# usb64.net
KiCad netlist of a schematic drawn in EAGLE
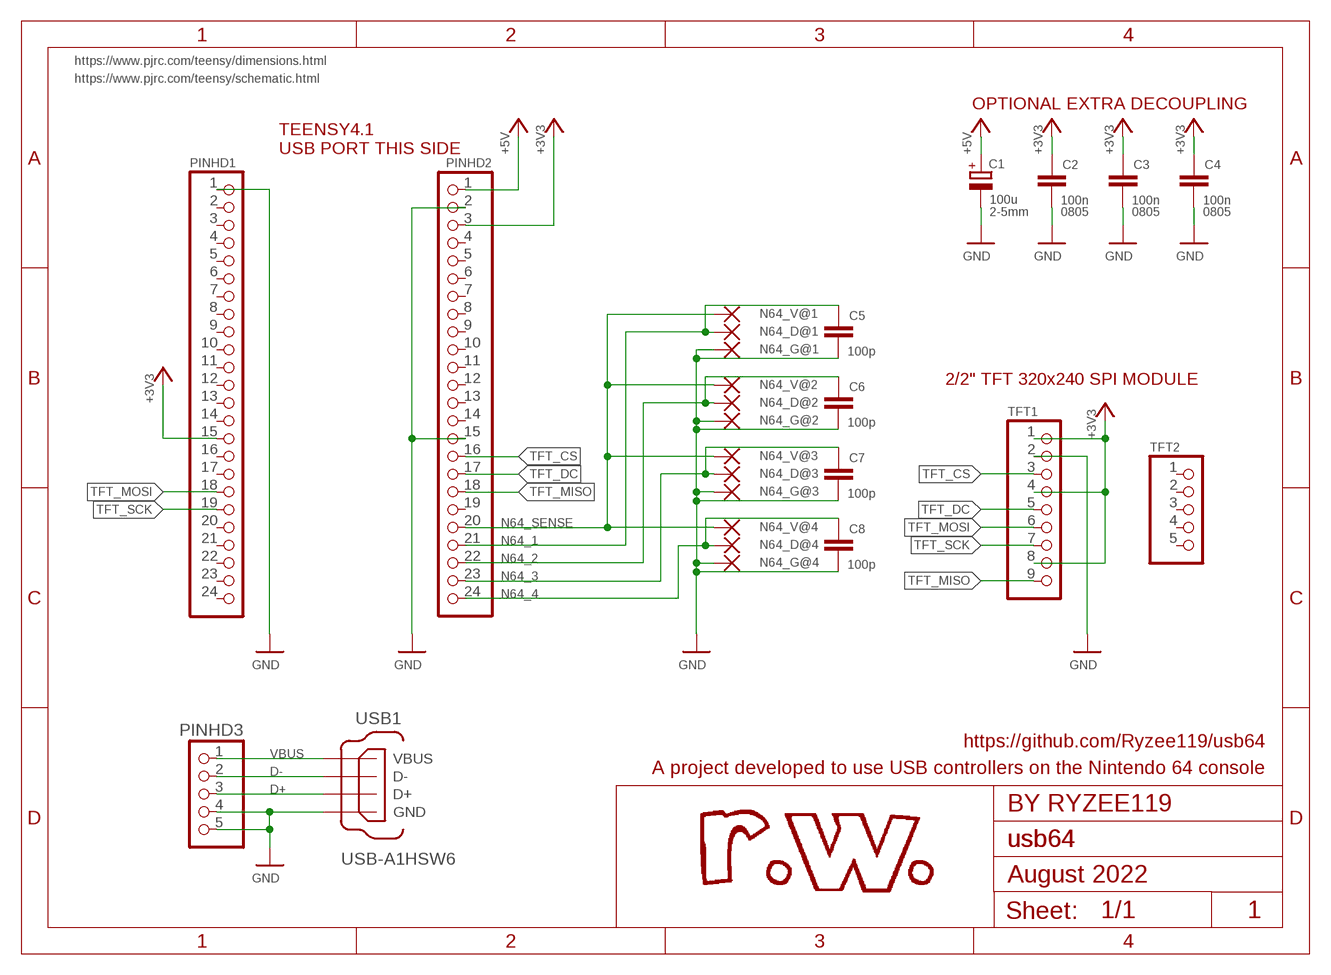
[diagram p0: schematic, sheet 1]

(export (version "E")
  (design (tool "Eeschema 10.0.6"))
  (components
    (comp (ref "C1")
      (value "100u")
      (footprint "eagle-import:E2-5")
      (libsource (lib "eagle-import") (part "CPOL-EUE2-5"))
    )
    (comp (ref "C2")
      (value "100n")
      (footprint "eagle-import:C0805K")
      (libsource (lib "eagle-import") (part "C-EUC0805K"))
    )
    (comp (ref "C3")
      (value "100n")
      (footprint "eagle-import:C0805K")
      (libsource (lib "eagle-import") (part "C-EUC0805K"))
    )
    (comp (ref "C4")
      (value "100n")
      (footprint "eagle-import:C0805K")
      (libsource (lib "eagle-import") (part "C-EUC0805K"))
    )
    (comp (ref "C5")
      (value "100p")
      (footprint "eagle-import:C0805K")
      (libsource (lib "eagle-import") (part "C-EUC0805K"))
    )
    (comp (ref "C6")
      (value "100p")
      (footprint "eagle-import:C0805K")
      (libsource (lib "eagle-import") (part "C-EUC0805K"))
    )
    (comp (ref "C7")
      (value "100p")
      (footprint "eagle-import:C0805K")
      (libsource (lib "eagle-import") (part "C-EUC0805K"))
    )
    (comp (ref "C8")
      (value "100p")
      (footprint "eagle-import:C0805K")
      (libsource (lib "eagle-import") (part "C-EUC0805K"))
    )
    (comp (ref "N64_D@1")
      (value "SMD2")
      (footprint "eagle-import:SMD1,27-2,54")
      (libsource (lib "eagle-import") (part "SMD2"))
    )
    (comp (ref "N64_D@2")
      (value "SMD2")
      (footprint "eagle-import:SMD1,27-2,54")
      (libsource (lib "eagle-import") (part "SMD2"))
    )
    (comp (ref "N64_D@3")
      (value "SMD2")
      (footprint "eagle-import:SMD1,27-2,54")
      (libsource (lib "eagle-import") (part "SMD2"))
    )
    (comp (ref "N64_D@4")
      (value "SMD2")
      (footprint "eagle-import:SMD1,27-2,54")
      (libsource (lib "eagle-import") (part "SMD2"))
    )
    (comp (ref "N64_G@1")
      (value "SMD2")
      (footprint "eagle-import:SMD1,27-2,54")
      (libsource (lib "eagle-import") (part "SMD2"))
    )
    (comp (ref "N64_G@2")
      (value "SMD2")
      (footprint "eagle-import:SMD1,27-2,54")
      (libsource (lib "eagle-import") (part "SMD2"))
    )
    (comp (ref "N64_G@3")
      (value "SMD2")
      (footprint "eagle-import:SMD1,27-2,54")
      (libsource (lib "eagle-import") (part "SMD2"))
    )
    (comp (ref "N64_G@4")
      (value "SMD2")
      (footprint "eagle-import:SMD1,27-2,54")
      (libsource (lib "eagle-import") (part "SMD2"))
    )
    (comp (ref "N64_V@1")
      (value "SMD2")
      (footprint "eagle-import:SMD1,27-2,54")
      (libsource (lib "eagle-import") (part "SMD2"))
    )
    (comp (ref "N64_V@2")
      (value "SMD2")
      (footprint "eagle-import:SMD1,27-2,54")
      (libsource (lib "eagle-import") (part "SMD2"))
    )
    (comp (ref "N64_V@3")
      (value "SMD2")
      (footprint "eagle-import:SMD1,27-2,54")
      (libsource (lib "eagle-import") (part "SMD2"))
    )
    (comp (ref "N64_V@4")
      (value "SMD2")
      (footprint "eagle-import:SMD1,27-2,54")
      (libsource (lib "eagle-import") (part "SMD2"))
    )
    (comp (ref "PINHD1")
      (value "PINHD-1X24")
      (footprint "eagle-import:1X24")
      (libsource (lib "eagle-import") (part "PINHD-1X24"))
    )
    (comp (ref "PINHD2")
      (value "PINHD-1X24")
      (footprint "eagle-import:1X24")
      (libsource (lib "eagle-import") (part "PINHD-1X24"))
    )
    (comp (ref "PINHD3")
      (value "PINHD-1X5")
      (footprint "eagle-import:1X05")
      (libsource (lib "eagle-import") (part "PINHD-1X5"))
    )
    (comp (ref "TFT1")
      (value "PINHD-1X9")
      (footprint "eagle-import:1X09")
      (libsource (lib "eagle-import") (part "PINHD-1X9"))
    )
    (comp (ref "TFT2")
      (value "PINHD-1X5")
      (footprint "eagle-import:1X05")
      (libsource (lib "eagle-import") (part "PINHD-1X5"))
    )
    (comp (ref "USB1")
      (value "USB-A1HSW6")
      (footprint "eagle-import:OST_USB-A1HSW6")
      (fields (field (name "DIGI-KEY_PART_NUMBER") "ED2989-ND") (field (name "MF") "On Shore"))
      (libsource (lib "eagle-import") (part "USB-A1HSW6"))
    )
  )
  (nets
    (net (code "1") (name "+3V3") (class "Default")
      (node (ref "C2") (pin "1") (pinfunction "1_1") (pintype "passive"))
      (node (ref "C3") (pin "1") (pinfunction "1_1") (pintype "passive"))
      (node (ref "C4") (pin "1") (pinfunction "1_1") (pintype "passive"))
      (node (ref "PINHD1") (pin "15") (pinfunction "15_15") (pintype "passive"))
      (node (ref "PINHD2") (pin "3") (pinfunction "3_3") (pintype "passive"))
      (node (ref "TFT1") (pin "1") (pinfunction "1_1") (pintype "passive"))
      (node (ref "TFT1") (pin "4") (pinfunction "4_4") (pintype "passive"))
      (node (ref "TFT1") (pin "8") (pinfunction "8_8") (pintype "passive"))
    )
    (net (code "2") (name "+5V") (class "Default")
      (node (ref "C1") (pin "+") (pinfunction "+_+") (pintype "passive"))
      (node (ref "PINHD2") (pin "1") (pinfunction "1_1") (pintype "passive"))
    )
    (net (code "3") (name "/D+") (class "Default")
      (node (ref "PINHD3") (pin "3") (pinfunction "3_3") (pintype "passive"))
      (node (ref "USB1") (pin "3") (pinfunction "D+_3") (pintype "bidirectional"))
    )
    (net (code "4") (name "/D-") (class "Default")
      (node (ref "PINHD3") (pin "2") (pinfunction "2_2") (pintype "passive"))
      (node (ref "USB1") (pin "2") (pinfunction "D-_2") (pintype "bidirectional"))
    )
    (net (code "5") (name "/N64_1") (class "Default")
      (node (ref "C5") (pin "1") (pinfunction "1_1") (pintype "passive"))
      (node (ref "N64_D@1") (pin "1") (pinfunction "P_1") (pintype "passive"))
      (node (ref "PINHD2") (pin "21") (pinfunction "21_21") (pintype "passive"))
    )
    (net (code "6") (name "/N64_2") (class "Default")
      (node (ref "C6") (pin "1") (pinfunction "1_1") (pintype "passive"))
      (node (ref "N64_D@2") (pin "1") (pinfunction "P_1") (pintype "passive"))
      (node (ref "PINHD2") (pin "22") (pinfunction "22_22") (pintype "passive"))
    )
    (net (code "7") (name "/N64_3") (class "Default")
      (node (ref "C7") (pin "1") (pinfunction "1_1") (pintype "passive"))
      (node (ref "N64_D@3") (pin "1") (pinfunction "P_1") (pintype "passive"))
      (node (ref "PINHD2") (pin "23") (pinfunction "23_23") (pintype "passive"))
    )
    (net (code "8") (name "/N64_4") (class "Default")
      (node (ref "C8") (pin "1") (pinfunction "1_1") (pintype "passive"))
      (node (ref "N64_D@4") (pin "1") (pinfunction "P_1") (pintype "passive"))
      (node (ref "PINHD2") (pin "24") (pinfunction "24_24") (pintype "passive"))
    )
    (net (code "9") (name "/N64_SENSE") (class "Default")
      (node (ref "N64_V@1") (pin "1") (pinfunction "P_1") (pintype "passive"))
      (node (ref "N64_V@2") (pin "1") (pinfunction "P_1") (pintype "passive"))
      (node (ref "N64_V@3") (pin "1") (pinfunction "P_1") (pintype "passive"))
      (node (ref "N64_V@4") (pin "1") (pinfunction "P_1") (pintype "passive"))
      (node (ref "PINHD2") (pin "20") (pinfunction "20_20") (pintype "passive"))
    )
    (net (code "10") (name "/VBUS") (class "Default")
      (node (ref "PINHD3") (pin "1") (pinfunction "1_1") (pintype "passive"))
      (node (ref "USB1") (pin "1") (pinfunction "VBUS_1") (pintype "power_in"))
    )
    (net (code "11") (name "GND") (class "Default")
      (node (ref "C1") (pin "-") (pinfunction "-_-") (pintype "passive"))
      (node (ref "C2") (pin "2") (pinfunction "2_2") (pintype "passive"))
      (node (ref "C3") (pin "2") (pinfunction "2_2") (pintype "passive"))
      (node (ref "C4") (pin "2") (pinfunction "2_2") (pintype "passive"))
      (node (ref "C5") (pin "2") (pinfunction "2_2") (pintype "passive"))
      (node (ref "C6") (pin "2") (pinfunction "2_2") (pintype "passive"))
      (node (ref "C7") (pin "2") (pinfunction "2_2") (pintype "passive"))
      (node (ref "C8") (pin "2") (pinfunction "2_2") (pintype "passive"))
      (node (ref "N64_G@1") (pin "1") (pinfunction "P_1") (pintype "passive"))
      (node (ref "N64_G@2") (pin "1") (pinfunction "P_1") (pintype "passive"))
      (node (ref "N64_G@3") (pin "1") (pinfunction "P_1") (pintype "passive"))
      (node (ref "N64_G@4") (pin "1") (pinfunction "P_1") (pintype "passive"))
      (node (ref "PINHD1") (pin "1") (pinfunction "1_1") (pintype "passive"))
      (node (ref "PINHD2") (pin "15") (pinfunction "15_15") (pintype "passive"))
      (node (ref "PINHD2") (pin "2") (pinfunction "2_2") (pintype "passive"))
      (node (ref "PINHD3") (pin "4") (pinfunction "4_4") (pintype "passive"))
      (node (ref "PINHD3") (pin "5") (pinfunction "5_5") (pintype "passive"))
      (node (ref "TFT1") (pin "2") (pinfunction "2_2") (pintype "passive"))
      (node (ref "USB1") (pin "4") (pinfunction "GND_4") (pintype "power_in"))
    )
    (net (code "12") (name "TFT_CS") (class "Default")
      (node (ref "PINHD2") (pin "16") (pinfunction "16_16") (pintype "passive"))
      (node (ref "TFT1") (pin "3") (pinfunction "3_3") (pintype "passive"))
    )
    (net (code "13") (name "TFT_DC") (class "Default")
      (node (ref "PINHD2") (pin "17") (pinfunction "17_17") (pintype "passive"))
      (node (ref "TFT1") (pin "5") (pinfunction "5_5") (pintype "passive"))
    )
    (net (code "14") (name "TFT_MISO") (class "Default")
      (node (ref "PINHD2") (pin "18") (pinfunction "18_18") (pintype "passive"))
      (node (ref "TFT1") (pin "9") (pinfunction "9_9") (pintype "passive"))
    )
    (net (code "15") (name "TFT_MOSI") (class "Default")
      (node (ref "PINHD1") (pin "18") (pinfunction "18_18") (pintype "passive"))
      (node (ref "TFT1") (pin "6") (pinfunction "6_6") (pintype "passive"))
    )
    (net (code "16") (name "TFT_SCK") (class "Default")
      (node (ref "PINHD1") (pin "19") (pinfunction "19_19") (pintype "passive"))
      (node (ref "TFT1") (pin "7") (pinfunction "7_7") (pintype "passive"))
    )
    (net (code "17") (name "unconnected-(PINHD1-Pad2)") (class "Default")
      (node (ref "PINHD1") (pin "2") (pinfunction "2_2") (pintype "passive"))
    )
    (net (code "18") (name "unconnected-(PINHD1-Pad3)") (class "Default")
      (node (ref "PINHD1") (pin "3") (pinfunction "3_3") (pintype "passive"))
    )
    (net (code "19") (name "unconnected-(PINHD1-Pad4)") (class "Default")
      (node (ref "PINHD1") (pin "4") (pinfunction "4_4") (pintype "passive"))
    )
    (net (code "20") (name "unconnected-(PINHD1-Pad5)") (class "Default")
      (node (ref "PINHD1") (pin "5") (pinfunction "5_5") (pintype "passive"))
    )
    (net (code "21") (name "unconnected-(PINHD1-Pad6)") (class "Default")
      (node (ref "PINHD1") (pin "6") (pinfunction "6_6") (pintype "passive"))
    )
    (net (code "22") (name "unconnected-(PINHD1-Pad7)") (class "Default")
      (node (ref "PINHD1") (pin "7") (pinfunction "7_7") (pintype "passive"))
    )
    (net (code "23") (name "unconnected-(PINHD1-Pad8)") (class "Default")
      (node (ref "PINHD1") (pin "8") (pinfunction "8_8") (pintype "passive"))
    )
    (net (code "24") (name "unconnected-(PINHD1-Pad9)") (class "Default")
      (node (ref "PINHD1") (pin "9") (pinfunction "9_9") (pintype "passive"))
    )
    (net (code "25") (name "unconnected-(PINHD1-Pad10)") (class "Default")
      (node (ref "PINHD1") (pin "10") (pinfunction "10_10") (pintype "passive"))
    )
    (net (code "26") (name "unconnected-(PINHD1-Pad11)") (class "Default")
      (node (ref "PINHD1") (pin "11") (pinfunction "11_11") (pintype "passive"))
    )
    (net (code "27") (name "unconnected-(PINHD1-Pad12)") (class "Default")
      (node (ref "PINHD1") (pin "12") (pinfunction "12_12") (pintype "passive"))
    )
    (net (code "28") (name "unconnected-(PINHD1-Pad13)") (class "Default")
      (node (ref "PINHD1") (pin "13") (pinfunction "13_13") (pintype "passive"))
    )
    (net (code "29") (name "unconnected-(PINHD1-Pad14)") (class "Default")
      (node (ref "PINHD1") (pin "14") (pinfunction "14_14") (pintype "passive"))
    )
    (net (code "30") (name "unconnected-(PINHD1-Pad16)") (class "Default")
      (node (ref "PINHD1") (pin "16") (pinfunction "16_16") (pintype "passive"))
    )
    (net (code "31") (name "unconnected-(PINHD1-Pad17)") (class "Default")
      (node (ref "PINHD1") (pin "17") (pinfunction "17_17") (pintype "passive"))
    )
    (net (code "32") (name "unconnected-(PINHD1-Pad20)") (class "Default")
      (node (ref "PINHD1") (pin "20") (pinfunction "20_20") (pintype "passive"))
    )
    (net (code "33") (name "unconnected-(PINHD1-Pad21)") (class "Default")
      (node (ref "PINHD1") (pin "21") (pinfunction "21_21") (pintype "passive"))
    )
    (net (code "34") (name "unconnected-(PINHD1-Pad22)") (class "Default")
      (node (ref "PINHD1") (pin "22") (pinfunction "22_22") (pintype "passive"))
    )
    (net (code "35") (name "unconnected-(PINHD1-Pad23)") (class "Default")
      (node (ref "PINHD1") (pin "23") (pinfunction "23_23") (pintype "passive"))
    )
    (net (code "36") (name "unconnected-(PINHD1-Pad24)") (class "Default")
      (node (ref "PINHD1") (pin "24") (pinfunction "24_24") (pintype "passive"))
    )
    (net (code "37") (name "unconnected-(PINHD2-Pad4)") (class "Default")
      (node (ref "PINHD2") (pin "4") (pinfunction "4_4") (pintype "passive"))
    )
    (net (code "38") (name "unconnected-(PINHD2-Pad5)") (class "Default")
      (node (ref "PINHD2") (pin "5") (pinfunction "5_5") (pintype "passive"))
    )
    (net (code "39") (name "unconnected-(PINHD2-Pad6)") (class "Default")
      (node (ref "PINHD2") (pin "6") (pinfunction "6_6") (pintype "passive"))
    )
    (net (code "40") (name "unconnected-(PINHD2-Pad7)") (class "Default")
      (node (ref "PINHD2") (pin "7") (pinfunction "7_7") (pintype "passive"))
    )
    (net (code "41") (name "unconnected-(PINHD2-Pad8)") (class "Default")
      (node (ref "PINHD2") (pin "8") (pinfunction "8_8") (pintype "passive"))
    )
    (net (code "42") (name "unconnected-(PINHD2-Pad9)") (class "Default")
      (node (ref "PINHD2") (pin "9") (pinfunction "9_9") (pintype "passive"))
    )
    (net (code "43") (name "unconnected-(PINHD2-Pad10)") (class "Default")
      (node (ref "PINHD2") (pin "10") (pinfunction "10_10") (pintype "passive"))
    )
    (net (code "44") (name "unconnected-(PINHD2-Pad11)") (class "Default")
      (node (ref "PINHD2") (pin "11") (pinfunction "11_11") (pintype "passive"))
    )
    (net (code "45") (name "unconnected-(PINHD2-Pad12)") (class "Default")
      (node (ref "PINHD2") (pin "12") (pinfunction "12_12") (pintype "passive"))
    )
    (net (code "46") (name "unconnected-(PINHD2-Pad13)") (class "Default")
      (node (ref "PINHD2") (pin "13") (pinfunction "13_13") (pintype "passive"))
    )
    (net (code "47") (name "unconnected-(PINHD2-Pad14)") (class "Default")
      (node (ref "PINHD2") (pin "14") (pinfunction "14_14") (pintype "passive"))
    )
    (net (code "48") (name "unconnected-(PINHD2-Pad19)") (class "Default")
      (node (ref "PINHD2") (pin "19") (pinfunction "19_19") (pintype "passive"))
    )
    (net (code "49") (name "unconnected-(TFT2-Pad1)") (class "Default")
      (node (ref "TFT2") (pin "1") (pinfunction "1_1") (pintype "passive"))
    )
    (net (code "50") (name "unconnected-(TFT2-Pad2)") (class "Default")
      (node (ref "TFT2") (pin "2") (pinfunction "2_2") (pintype "passive"))
    )
    (net (code "51") (name "unconnected-(TFT2-Pad3)") (class "Default")
      (node (ref "TFT2") (pin "3") (pinfunction "3_3") (pintype "passive"))
    )
    (net (code "52") (name "unconnected-(TFT2-Pad4)") (class "Default")
      (node (ref "TFT2") (pin "4") (pinfunction "4_4") (pintype "passive"))
    )
    (net (code "53") (name "unconnected-(TFT2-Pad5)") (class "Default")
      (node (ref "TFT2") (pin "5") (pinfunction "5_5") (pintype "passive"))
    )
  )
)
